# Voltage_Regulators.net
KiCad netlist of a schematic drawn in Altium Designer
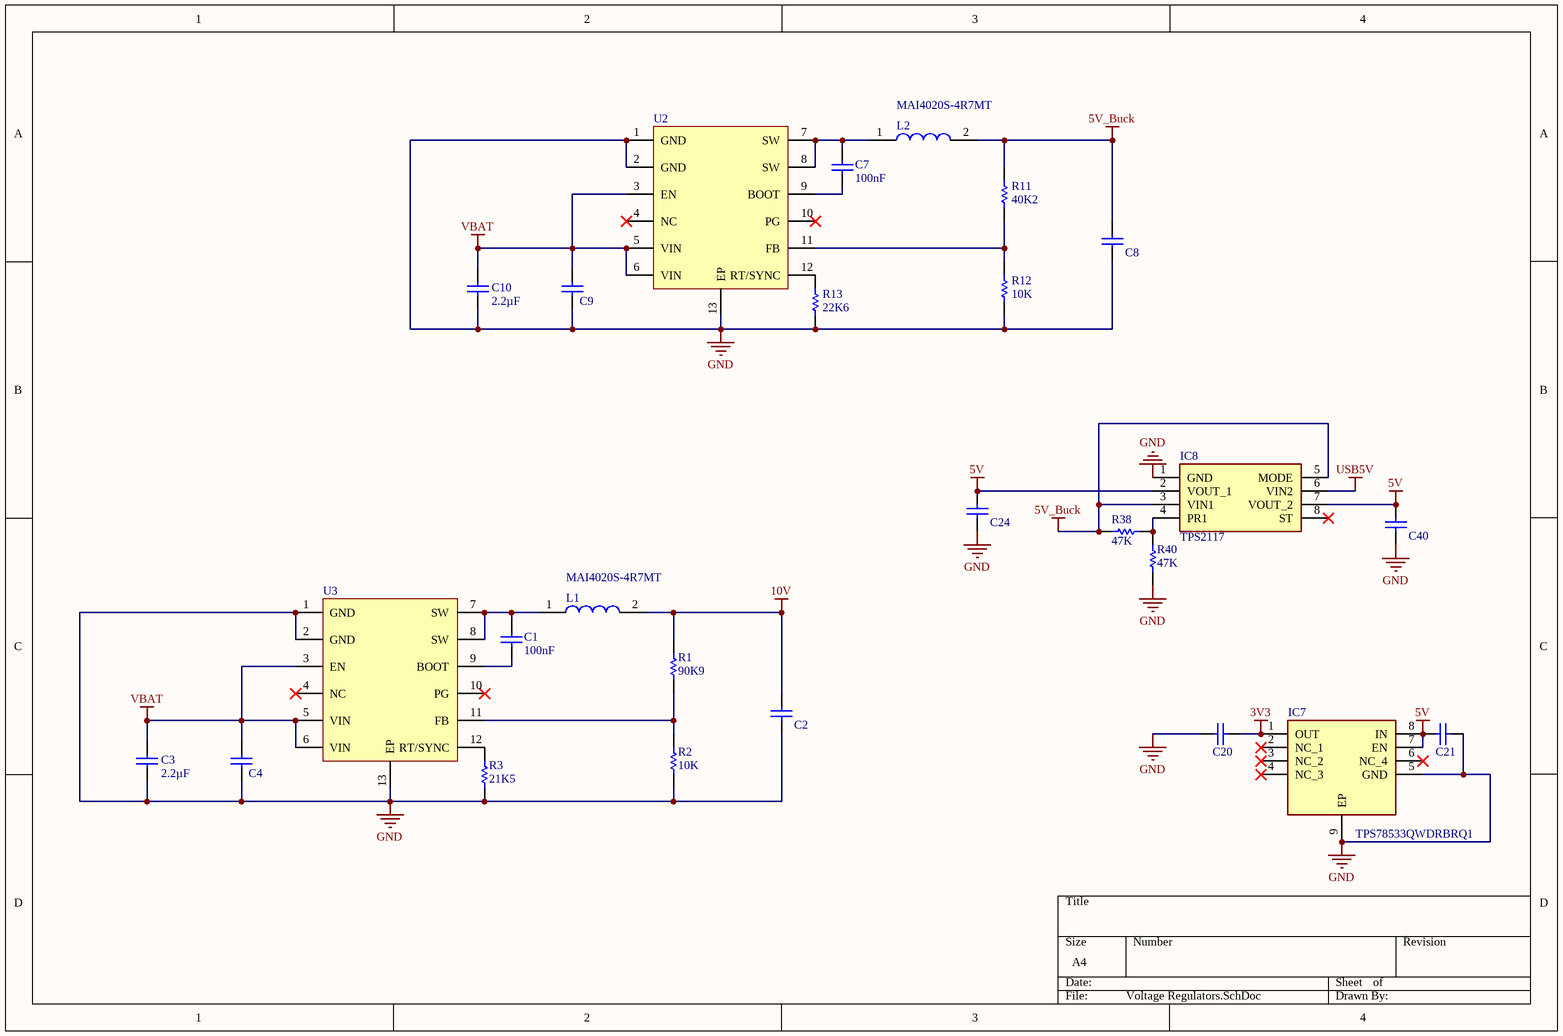
[diagram p0: Voltage Regulators.SchDoc]

(export (version "E")
  (design (tool "Eeschema 10.0.6"))
  (components
    (comp (ref "C1")
      (value "100nF")
      (footprint "0402 cap")
      (libsource (lib "Custom Components") (part "Capacitor 0402 100nF"))
    )
    (comp (ref "C2")
      (value "22µF")
      (footprint "WCAP-CSGP_1210_L3.2W2.5H2.5")
      (description "WCAP-CSGP Multilayer Ceramic Chip Capacitor, General Purpose, size 1210, X7R, 22µF, 25VDC")
      (fields
        (field (name "MANUFACTURER PART NUMBER") "885012209074")
        (field (name "MANUFACTURER") "Wurth Elektronik")
      )
      (libsource (lib "Altium_WCAP-CSGP (rev22f)") (part "885012209074"))
    )
    (comp (ref "C3")
      (value "2.2µF")
      (footprint "WCAP-CSGP_1206_L3.2W1.6H1.6")
      (description "WCAP-CSGP Multilayer Ceramic Chip Capacitor, General Purpose, size 1206, X7R, 2.2µF, 100VDC")
      (fields
        (field (name "MANUFACTURER PART NUMBER") "885012208124")
        (field (name "MANUFACTURER") "Wurth Elektronik")
      )
      (libsource (lib "Altium_WCAP-CSGP (rev22f)") (part "885012208124"))
    )
    (comp (ref "C4")
      (value "100nF")
      (footprint "WCAP-CSGP_0603_L1.6W0.8H0.8_Reflow")
      (description "WCAP-CSGP Multilayer Ceramic Chip Capacitor, General Purpose, size 0603, X7R, 100nF, 50VDC")
      (fields
        (field (name "MANUFACTURER PART NUMBER") "885012206095")
        (field (name "MANUFACTURER") "Wurth Elektronik")
      )
      (libsource (lib "Altium_WCAP-CSGP (rev22f)") (part "885012206095"))
    )
    (comp (ref "C7")
      (value "100nF")
      (footprint "0402 cap")
      (libsource (lib "Custom Components") (part "Capacitor 0402 100nF"))
    )
    (comp (ref "C8")
      (value "47µF")
      (footprint "WCAP-CSGP_1206_L3.2W1.6H1.6")
      (description "WCAP-CSGP Multilayer Ceramic Chip Capacitor, General Purpose, size 1206, X5R, 47µF, 10VDC")
      (fields
        (field (name "MANUFACTURER PART NUMBER") "885012108012")
        (field (name "MANUFACTURER") "Wurth Elektronik")
      )
      (libsource (lib "Altium_WCAP-CSGP (rev22f)") (part "885012108012"))
    )
    (comp (ref "C9")
      (value "100nF")
      (footprint "WCAP-CSGP_0603_L1.6W0.8H0.8_Reflow")
      (description "WCAP-CSGP Multilayer Ceramic Chip Capacitor, General Purpose, size 0603, X7R, 100nF, 50VDC")
      (fields
        (field (name "MANUFACTURER PART NUMBER") "885012206095")
        (field (name "MANUFACTURER") "Wurth Elektronik")
      )
      (libsource (lib "Altium_WCAP-CSGP (rev22f)") (part "885012206095"))
    )
    (comp (ref "C10")
      (value "2.2µF")
      (footprint "WCAP-CSGP_1206_L3.2W1.6H1.6")
      (description "WCAP-CSGP Multilayer Ceramic Chip Capacitor, General Purpose, size 1206, X7R, 2.2µF, 100VDC")
      (fields
        (field (name "MANUFACTURER PART NUMBER") "885012208124")
        (field (name "MANUFACTURER") "Wurth Elektronik")
      )
      (libsource (lib "Altium_WCAP-CSGP (rev22f)") (part "885012208124"))
    )
    (comp (ref "C20")
      (value "1µF")
      (footprint "WCAP-CSGP_0603_L1.6W0.8H0.8_Reflow")
      (description "WCAP-CSGP Multilayer Ceramic Chip Capacitor, General Purpose, size 0603, X7R, 1µF, 10VDC")
      (fields
        (field (name "MANUFACTURER PART NUMBER") "885012206026")
        (field (name "MANUFACTURER") "Wurth Elektronik")
      )
      (libsource (lib "Altium_WCAP-CSGP (rev22f)") (part "885012206026"))
    )
    (comp (ref "C21")
      (value "1µF")
      (footprint "WCAP-CSGP_0603_L1.6W0.8H0.8_Reflow")
      (description "WCAP-CSGP Multilayer Ceramic Chip Capacitor, General Purpose, size 0603, X7R, 1µF, 10VDC")
      (fields
        (field (name "MANUFACTURER PART NUMBER") "885012206026")
        (field (name "MANUFACTURER") "Wurth Elektronik")
      )
      (libsource (lib "Altium_WCAP-CSGP (rev22f)") (part "885012206026"))
    )
    (comp (ref "C24")
      (value "1µF")
      (footprint "WCAP-CSGP_0603_L1.6W0.8H0.8_Reflow")
      (description "WCAP-CSGP Multilayer Ceramic Chip Capacitor, General Purpose, size 0603, X5R, 1µF, 16VDC")
      (fields
        (field (name "MANUFACTURER PART NUMBER") "885012106017")
        (field (name "MANUFACTURER") "Wurth Elektronik")
      )
      (libsource (lib "Altium_WCAP-CSGP (rev22f)") (part "885012106017"))
    )
    (comp (ref "C40")
      (value "1µF")
      (footprint "WCAP-CSGP_0603_L1.6W0.8H0.8_Reflow")
      (description "WCAP-CSGP Multilayer Ceramic Chip Capacitor, General Purpose, size 0603, X5R, 1µF, 16VDC")
      (fields
        (field (name "MANUFACTURER PART NUMBER") "885012106017")
        (field (name "MANUFACTURER") "Wurth Elektronik")
      )
      (libsource (lib "Altium_WCAP-CSGP (rev22f)") (part "885012106017"))
    )
    (comp (ref "IC7")
      (value "TPS78533QWDRBRQ1")
      (footprint "Custom Components:SON65P300X300X100-9N-D")
      (description "Integrated Circuit")
      (fields (field (name "MOUSER PART NUMBER") "595-TPS78533QWDRBRQ1"))
      (libsource (lib "Custom Components") (part "TPS78533QWDRBRQ1"))
    )
    (comp (ref "IC8")
      (value "TPS2117")
      (footprint "Custom Components:SOTFL50P160X60-8N")
      (description "Integrated Circuit")
      (fields
        (field (name "MANUFACTURER_PART_NUMBER") "TPS2116DRLR")
        (field (name "MOUSER PART NUMBER") "595-TPS2116DRLR")
      )
      (libsource (lib "*") (part "TPS2116DRLR"))
    )
    (comp (ref "L1")
      (value "MAI4020S-4R7MT")
      (footprint "MAI4020S-4R7MT")
      (libsource (lib "Custom Components") (part "MAI4020S-4R7MT"))
    )
    (comp (ref "L2")
      (value "MAI4020S-4R7MT")
      (footprint "MAI4020S-4R7MT")
      (libsource (lib "Custom Components") (part "MAI4020S-4R7MT"))
    )
    (comp (ref "R1")
      (value "90K9")
      (footprint "Custom Components:0402 resistor")
      (libsource (lib "Custom Components") (part "Resistor 0402 1K"))
    )
    (comp (ref "R2")
      (value "10K")
      (footprint "Custom Components:0402 resistor")
      (libsource (lib "Custom Components") (part "Resistor 0402 1K"))
    )
    (comp (ref "R3")
      (value "21K5")
      (footprint "Custom Components:0402 resistor")
      (libsource (lib "Custom Components") (part "Resistor 0402 1K"))
    )
    (comp (ref "R11")
      (value "40K2")
      (footprint "RESC0603(1608)_N")
      (description "Chipwiderstand, SMD, Baureihe MC, 1%")
      (fields (field (name "MANUFACTURER") "Multicomp"))
      (libsource (lib "Standardbauteile") (part "Res 33K"))
    )
    (comp (ref "R12")
      (value "10K")
      (footprint "RESC0603(1608)_N")
      (description "Chipwiderstand, SMD, Baureihe MC, 1%")
      (fields (field (name "MANUFACTURER") "Multicomp"))
      (libsource (lib "Standardbauteile") (part "Res 33K"))
    )
    (comp (ref "R13")
      (value "22K6")
      (footprint "RESC0603(1608)_N")
      (description "Chipwiderstand, SMD, Baureihe MC, 1%")
      (fields (field (name "MANUFACTURER") "Multicomp"))
      (libsource (lib "Standardbauteile") (part "Res 33K"))
    )
    (comp (ref "R38")
      (value "47K")
      (footprint "Custom Components:0402 resistor")
      (libsource (lib "Custom Components") (part "Resistor 0402 1K"))
    )
    (comp (ref "R40")
      (value "47K")
      (footprint "Custom Components:0402 resistor")
      (libsource (lib "Custom Components") (part "Resistor 0402 1K"))
    )
    (comp (ref "U2")
      (value "2.5A Step Down QFN synchronous")
      (footprint "LMR38025")
      (libsource (lib "Custom Components") (part "LMR38025"))
    )
    (comp (ref "U3")
      (value "2.5A Step Down QFN synchronous")
      (footprint "LMR38025")
      (libsource (lib "Custom Components") (part "LMR38025"))
    )
  )
  (nets
    (net (code "1") (name "3V3") (class "Default")
      (node (ref "C20") (pin "2") (pinfunction "2_2") (pintype "passive"))
      (node (ref "IC7") (pin "1") (pinfunction "OUT_1") (pintype "passive"))
    )
    (net (code "2") (name "5V") (class "Default")
      (node (ref "C21") (pin "1") (pinfunction "1_1") (pintype "passive"))
      (node (ref "C24") (pin "2") (pinfunction "2_2") (pintype "passive"))
      (node (ref "C40") (pin "2") (pinfunction "2_2") (pintype "passive"))
      (node (ref "IC7") (pin "7") (pinfunction "EN_7") (pintype "passive"))
      (node (ref "IC7") (pin "8") (pinfunction "IN_8") (pintype "passive"))
      (node (ref "IC8") (pin "2") (pinfunction "VOUT_1_2") (pintype "passive"))
      (node (ref "IC8") (pin "7") (pinfunction "VOUT_2_7") (pintype "passive"))
    )
    (net (code "3") (name "5V_Buck") (class "Default")
      (node (ref "C8") (pin "2") (pinfunction "2_2") (pintype "passive"))
      (node (ref "IC8") (pin "3") (pinfunction "VIN1_3") (pintype "passive"))
      (node (ref "IC8") (pin "5") (pinfunction "MODE_5") (pintype "passive"))
      (node (ref "L2") (pin "2") (pinfunction "2_2") (pintype "passive"))
      (node (ref "R11") (pin "2") (pinfunction "2_2") (pintype "passive"))
      (node (ref "R38") (pin "1") (pinfunction "1_1") (pintype "passive"))
    )
    (net (code "4") (name "10V") (class "Default")
      (node (ref "C2") (pin "2") (pinfunction "2_2") (pintype "passive"))
      (node (ref "L1") (pin "2") (pinfunction "2_2") (pintype "passive"))
      (node (ref "R1") (pin "2") (pinfunction "2_2") (pintype "passive"))
    )
    (net (code "5") (name "GND") (class "Default")
      (node (ref "C10") (pin "1") (pinfunction "1_1") (pintype "passive"))
      (node (ref "C2") (pin "1") (pinfunction "1_1") (pintype "passive"))
      (node (ref "C20") (pin "1") (pinfunction "1_1") (pintype "passive"))
      (node (ref "C21") (pin "2") (pinfunction "2_2") (pintype "passive"))
      (node (ref "C24") (pin "1") (pinfunction "1_1") (pintype "passive"))
      (node (ref "C3") (pin "1") (pinfunction "1_1") (pintype "passive"))
      (node (ref "C4") (pin "1") (pinfunction "1_1") (pintype "passive"))
      (node (ref "C40") (pin "1") (pinfunction "1_1") (pintype "passive"))
      (node (ref "C8") (pin "1") (pinfunction "1_1") (pintype "passive"))
      (node (ref "C9") (pin "1") (pinfunction "1_1") (pintype "passive"))
      (node (ref "IC7") (pin "5") (pinfunction "GND_5") (pintype "passive"))
      (node (ref "IC7") (pin "9") (pinfunction "EP_9") (pintype "passive"))
      (node (ref "IC8") (pin "1") (pinfunction "GND_1") (pintype "passive"))
      (node (ref "R12") (pin "1") (pinfunction "1_1") (pintype "passive"))
      (node (ref "R13") (pin "1") (pinfunction "1_1") (pintype "passive"))
      (node (ref "R2") (pin "1") (pinfunction "1_1") (pintype "passive"))
      (node (ref "R3") (pin "1") (pinfunction "1_1") (pintype "passive"))
      (node (ref "R40") (pin "1") (pinfunction "1_1") (pintype "passive"))
      (node (ref "U2") (pin "1") (pinfunction "GND_1") (pintype "passive"))
      (node (ref "U2") (pin "13") (pinfunction "EP_13") (pintype "passive"))
      (node (ref "U2") (pin "2") (pinfunction "GND_2") (pintype "passive"))
      (node (ref "U3") (pin "1") (pinfunction "GND_1") (pintype "passive"))
      (node (ref "U3") (pin "13") (pinfunction "EP_13") (pintype "passive"))
      (node (ref "U3") (pin "2") (pinfunction "GND_2") (pintype "passive"))
    )
    (net (code "6") (name "Net-(C1-Pad2)") (class "Default")
      (node (ref "C1") (pin "2") (pinfunction "2_2") (pintype "passive"))
      (node (ref "L1") (pin "1") (pinfunction "1_1") (pintype "passive"))
      (node (ref "U3") (pin "7") (pinfunction "SW_7") (pintype "passive"))
      (node (ref "U3") (pin "8") (pinfunction "SW_8") (pintype "passive"))
    )
    (net (code "7") (name "Net-(C7-Pad2)") (class "Default")
      (node (ref "C7") (pin "2") (pinfunction "2_2") (pintype "passive"))
      (node (ref "L2") (pin "1") (pinfunction "1_1") (pintype "passive"))
      (node (ref "U2") (pin "7") (pinfunction "SW_7") (pintype "passive"))
      (node (ref "U2") (pin "8") (pinfunction "SW_8") (pintype "passive"))
    )
    (net (code "8") (name "Net-(IC8-PR1)") (class "Default")
      (node (ref "IC8") (pin "4") (pinfunction "PR1_4") (pintype "passive"))
      (node (ref "R38") (pin "2") (pinfunction "2_2") (pintype "passive"))
      (node (ref "R40") (pin "2") (pinfunction "2_2") (pintype "passive"))
    )
    (net (code "9") (name "Net-(U2-BOOT)") (class "Default")
      (node (ref "C7") (pin "1") (pinfunction "1_1") (pintype "passive"))
      (node (ref "U2") (pin "9") (pinfunction "BOOT_9") (pintype "passive"))
    )
    (net (code "10") (name "Net-(U2-FB)") (class "Default")
      (node (ref "R11") (pin "1") (pinfunction "1_1") (pintype "passive"))
      (node (ref "R12") (pin "2") (pinfunction "2_2") (pintype "passive"))
      (node (ref "U2") (pin "11") (pinfunction "FB_11") (pintype "passive"))
    )
    (net (code "11") (name "Net-(U2-RT{slash}SYNC)") (class "Default")
      (node (ref "R13") (pin "2") (pinfunction "2_2") (pintype "passive"))
      (node (ref "U2") (pin "12") (pinfunction "RT/SYNC_12") (pintype "passive"))
    )
    (net (code "12") (name "Net-(U3-BOOT)") (class "Default")
      (node (ref "C1") (pin "1") (pinfunction "1_1") (pintype "passive"))
      (node (ref "U3") (pin "9") (pinfunction "BOOT_9") (pintype "passive"))
    )
    (net (code "13") (name "Net-(U3-FB)") (class "Default")
      (node (ref "R1") (pin "1") (pinfunction "1_1") (pintype "passive"))
      (node (ref "R2") (pin "2") (pinfunction "2_2") (pintype "passive"))
      (node (ref "U3") (pin "11") (pinfunction "FB_11") (pintype "passive"))
    )
    (net (code "14") (name "Net-(U3-RT{slash}SYNC)") (class "Default")
      (node (ref "R3") (pin "2") (pinfunction "2_2") (pintype "passive"))
      (node (ref "U3") (pin "12") (pinfunction "RT/SYNC_12") (pintype "passive"))
    )
    (net (code "15") (name "USB5V") (class "Default")
      (node (ref "IC8") (pin "6") (pinfunction "VIN2_6") (pintype "passive"))
    )
    (net (code "16") (name "VBAT") (class "Default")
      (node (ref "C10") (pin "2") (pinfunction "2_2") (pintype "passive"))
      (node (ref "C3") (pin "2") (pinfunction "2_2") (pintype "passive"))
      (node (ref "C4") (pin "2") (pinfunction "2_2") (pintype "passive"))
      (node (ref "C9") (pin "2") (pinfunction "2_2") (pintype "passive"))
      (node (ref "U2") (pin "3") (pinfunction "EN_3") (pintype "passive"))
      (node (ref "U2") (pin "5") (pinfunction "VIN_5") (pintype "passive"))
      (node (ref "U2") (pin "6") (pinfunction "VIN_6") (pintype "passive"))
      (node (ref "U3") (pin "3") (pinfunction "EN_3") (pintype "passive"))
      (node (ref "U3") (pin "5") (pinfunction "VIN_5") (pintype "passive"))
      (node (ref "U3") (pin "6") (pinfunction "VIN_6") (pintype "passive"))
    )
    (net (code "17") (name "unconnected-(IC7-NC_1-Pad2)") (class "Default")
      (node (ref "IC7") (pin "2") (pinfunction "NC_1_2") (pintype "passive+no_connect"))
    )
    (net (code "18") (name "unconnected-(IC7-NC_2-Pad3)") (class "Default")
      (node (ref "IC7") (pin "3") (pinfunction "NC_2_3") (pintype "passive+no_connect"))
    )
    (net (code "19") (name "unconnected-(IC7-NC_3-Pad4)") (class "Default")
      (node (ref "IC7") (pin "4") (pinfunction "NC_3_4") (pintype "passive+no_connect"))
    )
    (net (code "20") (name "unconnected-(IC7-NC_4-Pad6)") (class "Default")
      (node (ref "IC7") (pin "6") (pinfunction "NC_4_6") (pintype "passive+no_connect"))
    )
    (net (code "21") (name "unconnected-(IC8-ST-Pad8)") (class "Default")
      (node (ref "IC8") (pin "8") (pinfunction "ST_8") (pintype "passive+no_connect"))
    )
    (net (code "22") (name "unconnected-(U2-NC-Pad4)") (class "Default")
      (node (ref "U2") (pin "4") (pinfunction "NC_4") (pintype "passive+no_connect"))
    )
    (net (code "23") (name "unconnected-(U2-PG-Pad10)") (class "Default")
      (node (ref "U2") (pin "10") (pinfunction "PG_10") (pintype "passive+no_connect"))
    )
    (net (code "24") (name "unconnected-(U3-NC-Pad4)") (class "Default")
      (node (ref "U3") (pin "4") (pinfunction "NC_4") (pintype "passive+no_connect"))
    )
    (net (code "25") (name "unconnected-(U3-PG-Pad10)") (class "Default")
      (node (ref "U3") (pin "10") (pinfunction "PG_10") (pintype "passive+no_connect"))
    )
  )
)
